# lan.net
KiCad netlist of a schematic drawn in EAGLE
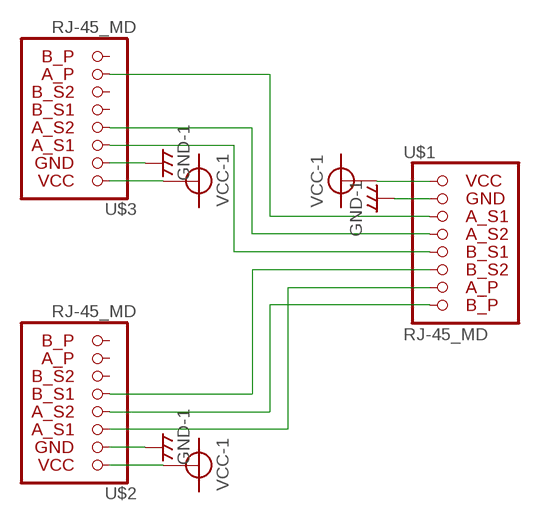
[diagram p0: schematic, sheet 1]

(export (version "E")
  (design (tool "Eeschema 10.0.6"))
  (components
    (comp (ref "U$1")
      (value "RJ-45_MD")
      (footprint "eagle-import:996-A2-1188A2")
      (libsource (lib "eagle-import") (part "RJ-45_MD"))
    )
    (comp (ref "U$2")
      (value "RJ-45_MD")
      (footprint "eagle-import:996-A2-1188A2")
      (libsource (lib "eagle-import") (part "RJ-45_MD"))
    )
    (comp (ref "U$3")
      (value "RJ-45_MD")
      (footprint "eagle-import:996-A2-1188A2")
      (libsource (lib "eagle-import") (part "RJ-45_MD"))
    )
  )
  (nets
    (net (code "1") (name "GND-1") (class "Default")
      (node (ref "U$1") (pin "2") (pinfunction "P$2_2") (pintype "bidirectional"))
      (node (ref "U$2") (pin "2") (pinfunction "P$2_2") (pintype "bidirectional"))
      (node (ref "U$3") (pin "2") (pinfunction "P$2_2") (pintype "bidirectional"))
    )
    (net (code "2") (name "Net-(U$1-P$3)") (class "Default")
      (node (ref "U$1") (pin "3") (pinfunction "P$3_3") (pintype "bidirectional"))
      (node (ref "U$3") (pin "7") (pinfunction "P$7_7") (pintype "bidirectional"))
    )
    (net (code "3") (name "Net-(U$1-P$4)") (class "Default")
      (node (ref "U$1") (pin "4") (pinfunction "P$4_4") (pintype "bidirectional"))
      (node (ref "U$3") (pin "4") (pinfunction "P$4_4") (pintype "bidirectional"))
    )
    (net (code "4") (name "Net-(U$1-P$5)") (class "Default")
      (node (ref "U$1") (pin "5") (pinfunction "P$5_5") (pintype "bidirectional"))
      (node (ref "U$3") (pin "3") (pinfunction "P$3_3") (pintype "bidirectional"))
    )
    (net (code "5") (name "Net-(U$1-P$6)") (class "Default")
      (node (ref "U$1") (pin "6") (pinfunction "P$6_6") (pintype "bidirectional"))
      (node (ref "U$2") (pin "5") (pinfunction "P$5_5") (pintype "bidirectional"))
    )
    (net (code "6") (name "Net-(U$1-P$7)") (class "Default")
      (node (ref "U$1") (pin "7") (pinfunction "P$7_7") (pintype "bidirectional"))
      (node (ref "U$2") (pin "3") (pinfunction "P$3_3") (pintype "bidirectional"))
    )
    (net (code "7") (name "Net-(U$1-P$8)") (class "Default")
      (node (ref "U$1") (pin "8") (pinfunction "P$8_8") (pintype "bidirectional"))
      (node (ref "U$2") (pin "4") (pinfunction "P$4_4") (pintype "bidirectional"))
    )
    (net (code "8") (name "VCC-1") (class "Default")
      (node (ref "U$1") (pin "1") (pinfunction "P$1_1") (pintype "bidirectional"))
      (node (ref "U$2") (pin "1") (pinfunction "P$1_1") (pintype "bidirectional"))
      (node (ref "U$3") (pin "1") (pinfunction "P$1_1") (pintype "bidirectional"))
    )
    (net (code "9") (name "unconnected-(U$2-P$6-Pad6)") (class "Default")
      (node (ref "U$2") (pin "6") (pinfunction "P$6_6") (pintype "bidirectional"))
    )
    (net (code "10") (name "unconnected-(U$2-P$7-Pad7)") (class "Default")
      (node (ref "U$2") (pin "7") (pinfunction "P$7_7") (pintype "bidirectional"))
    )
    (net (code "11") (name "unconnected-(U$2-P$8-Pad8)") (class "Default")
      (node (ref "U$2") (pin "8") (pinfunction "P$8_8") (pintype "bidirectional"))
    )
    (net (code "12") (name "unconnected-(U$3-P$5-Pad5)") (class "Default")
      (node (ref "U$3") (pin "5") (pinfunction "P$5_5") (pintype "bidirectional"))
    )
    (net (code "13") (name "unconnected-(U$3-P$6-Pad6)") (class "Default")
      (node (ref "U$3") (pin "6") (pinfunction "P$6_6") (pintype "bidirectional"))
    )
    (net (code "14") (name "unconnected-(U$3-P$8-Pad8)") (class "Default")
      (node (ref "U$3") (pin "8") (pinfunction "P$8_8") (pintype "bidirectional"))
    )
  )
)
